# Dust1_Motherboard_Peripheral.net
KiCad netlist of a schematic drawn in Altium Designer
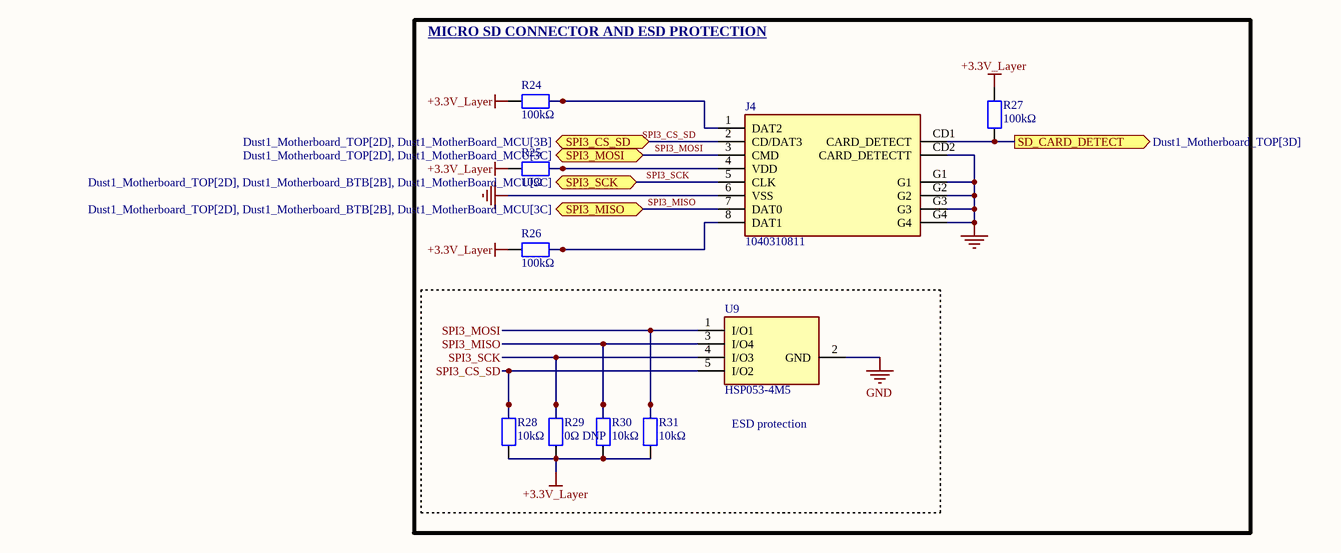
[diagram p0: Dust1_Motherboard_Peripheral.SchDoc]

(export (version "E")
  (design (tool "Eeschema 10.0.6"))
  (components
    (comp (ref "J4")
      (value "1040310811")
      (footprint "1040310811")
      (libsource (lib "I3N - LABSAMP") (part "SD CARD"))
    )
    (comp (ref "R24")
      (value "100kΩ")
      (footprint "RES_0402")
      (description "Resistor SMD 0402 Generic")
      (libsource (lib "I3N - LABSAMP") (part "RES_0402"))
    )
    (comp (ref "R25")
      (value "10Ω")
      (footprint "RES_0402")
      (description "Resistor SMD 0402 Generic")
      (libsource (lib "I3N - LABSAMP") (part "RES_0402"))
    )
    (comp (ref "R26")
      (value "100kΩ")
      (footprint "RES_0402")
      (description "Resistor SMD 0402 Generic")
      (libsource (lib "I3N - LABSAMP") (part "RES_0402"))
    )
    (comp (ref "R27")
      (value "100kΩ")
      (footprint "RES_0402")
      (description "Resistor SMD 0402 Generic")
      (libsource (lib "I3N - LABSAMP") (part "RES_0402"))
    )
    (comp (ref "R28")
      (value "10kΩ")
      (footprint "RES_0402")
      (description "Resistor SMD 0402 Generic")
      (libsource (lib "I3N - LABSAMP") (part "RES_0402"))
    )
    (comp (ref "R29")
      (value "0Ω DNP")
      (footprint "RES_0402")
      (description "Resistor SMD 0402 Generic")
      (libsource (lib "I3N - LABSAMP") (part "RES_0402"))
    )
    (comp (ref "R30")
      (value "10kΩ")
      (footprint "RES_0402")
      (description "Resistor SMD 0402 Generic")
      (libsource (lib "I3N - LABSAMP") (part "RES_0402"))
    )
    (comp (ref "R31")
      (value "10kΩ")
      (footprint "RES_0402")
      (description "Resistor SMD 0402 Generic")
      (libsource (lib "I3N - LABSAMP") (part "RES_0402"))
    )
    (comp (ref "U9")
      (value "HSP053-4M5")
      (footprint "HSP0534M5")
      (description "Clamp Ipp Tvs Diode Surface Mount 5-uQFN (1.3x0.8)")
      (fields (field (name "MOUSER PART NUMBER") "511-HSP053-4M5"))
      (libsource (lib "I3N - LABSAMP") (part "HSP053-4M5"))
    )
  )
  (nets
    (net (code "1") (name "+3.3V_Layer") (class "Default")
      (node (ref "R24") (pin "2") (pintype "passive"))
      (node (ref "R25") (pin "2") (pintype "passive"))
      (node (ref "R26") (pin "2") (pintype "passive"))
      (node (ref "R27") (pin "2") (pintype "passive"))
      (node (ref "R28") (pin "1") (pintype "passive"))
      (node (ref "R29") (pin "1") (pintype "passive"))
      (node (ref "R30") (pin "1") (pintype "passive"))
      (node (ref "R31") (pin "1") (pintype "passive"))
    )
    (net (code "2") (name "/SD_CARD_DETECT") (class "Default")
      (node (ref "J4") (pin "CD1") (pinfunction "CARD_DETECT_CD1") (pintype "passive"))
      (node (ref "R27") (pin "1") (pintype "passive"))
    )
    (net (code "3") (name "/SPI3_CS_SD") (class "Default")
      (node (ref "J4") (pin "2") (pinfunction "CD/DAT3_2") (pintype "passive"))
      (node (ref "R28") (pin "2") (pintype "passive"))
      (node (ref "U9") (pin "5") (pinfunction "I/O2_5") (pintype "passive"))
    )
    (net (code "4") (name "/SPI3_MISO") (class "Default")
      (node (ref "J4") (pin "7") (pinfunction "DAT0_7") (pintype "passive"))
      (node (ref "R30") (pin "2") (pintype "passive"))
      (node (ref "U9") (pin "3") (pinfunction "I/O4_3") (pintype "passive"))
    )
    (net (code "5") (name "/SPI3_MOSI") (class "Default")
      (node (ref "J4") (pin "3") (pinfunction "CMD_3") (pintype "passive"))
      (node (ref "R31") (pin "2") (pintype "passive"))
      (node (ref "U9") (pin "1") (pinfunction "I/O1_1") (pintype "passive"))
    )
    (net (code "6") (name "/SPI3_SCK") (class "Default")
      (node (ref "J4") (pin "5") (pinfunction "CLK_5") (pintype "passive"))
      (node (ref "R29") (pin "2") (pintype "passive"))
      (node (ref "U9") (pin "4") (pinfunction "I/O3_4") (pintype "passive"))
    )
    (net (code "7") (name "GND") (class "Default")
      (node (ref "J4") (pin "6") (pinfunction "VSS_6") (pintype "passive"))
      (node (ref "J4") (pin "CD2") (pinfunction "CARD_DETECTT_CD2") (pintype "passive"))
      (node (ref "J4") (pin "G1") (pinfunction "G1_G1") (pintype "passive"))
      (node (ref "J4") (pin "G2") (pinfunction "G2_G2") (pintype "passive"))
      (node (ref "J4") (pin "G3") (pinfunction "G3_G3") (pintype "passive"))
      (node (ref "J4") (pin "G4") (pinfunction "G4_G4") (pintype "passive"))
      (node (ref "U9") (pin "2") (pinfunction "GND_2") (pintype "passive"))
    )
    (net (code "8") (name "Net-(J4-DAT1)") (class "Default")
      (node (ref "J4") (pin "8") (pinfunction "DAT1_8") (pintype "passive"))
      (node (ref "R26") (pin "1") (pintype "passive"))
    )
    (net (code "9") (name "Net-(J4-DAT2)") (class "Default")
      (node (ref "J4") (pin "1") (pinfunction "DAT2_1") (pintype "passive"))
      (node (ref "R24") (pin "1") (pintype "passive"))
    )
    (net (code "10") (name "Net-(J4-VDD)") (class "Default")
      (node (ref "J4") (pin "4") (pinfunction "VDD_4") (pintype "passive"))
      (node (ref "R25") (pin "1") (pintype "passive"))
    )
  )
)
